# Power_Source.net
KiCad netlist of a schematic drawn in Altium Designer
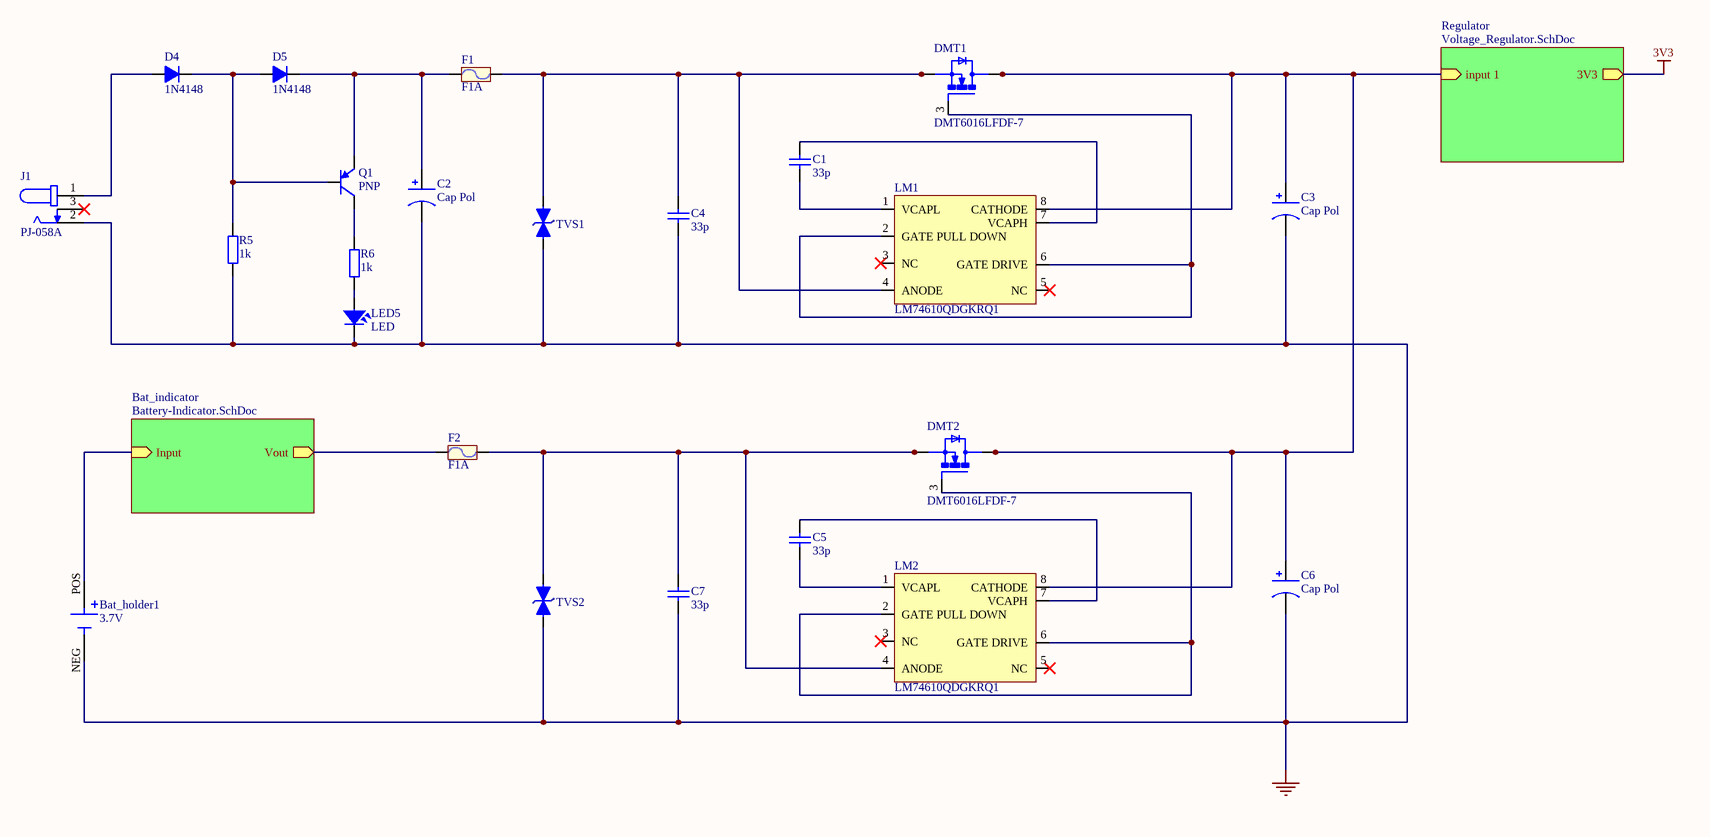
[diagram p0: Power_Source.SchDoc]

(export (version "E")
  (design (tool "Eeschema 10.0.6"))
  (components
    (comp (ref "Bat_holder1")
      (value "3.7V")
      (footprint "BAT_BK-18650-PC2")
      (description "Battery Holder (Open) 18650 1 Cell PC Pin")
      (fields (field (name "MP") "BK-18650-PC2"))
      (libsource (lib "BK-18650-PC2") (part "BK-18650-PC2"))
    )
    (comp (ref "C1")
      (value "33p")
      (footprint "CAP_CERAMIC")
      (description "Capacitor")
      (fields (field (name "Comment") "Capacitor Ceramic") (field (name "PUBLISHER") "Altium Limited"))
      (libsource (lib "My Library.~(1)") (part "CapCeramic"))
    )
    (comp (ref "C2")
      (value "Cap Pol")
      (footprint "C3MM")
      (description "Polarized Capacitor (Axial)")
      (fields (field (name "PUBLISHER") "Altium Limited"))
      (libsource (lib "My Library.~(1)") (part "Cap Pol"))
    )
    (comp (ref "C3")
      (value "Cap Pol")
      (footprint "C3MM")
      (description "Polarized Capacitor (Axial)")
      (fields (field (name "PUBLISHER") "Altium Limited"))
      (libsource (lib "My Library.~(1)") (part "Cap Pol"))
    )
    (comp (ref "C4")
      (value "33p")
      (footprint "CAP_CERAMIC")
      (description "Capacitor")
      (fields (field (name "Comment") "Capacitor Ceramic") (field (name "PUBLISHER") "Altium Limited"))
      (libsource (lib "My Library.~(1)") (part "CapCeramic"))
    )
    (comp (ref "C5")
      (value "33p")
      (footprint "CAP_CERAMIC")
      (description "Capacitor")
      (fields (field (name "Comment") "Capacitor Ceramic") (field (name "PUBLISHER") "Altium Limited"))
      (libsource (lib "My Library.~(1)") (part "CapCeramic"))
    )
    (comp (ref "C6")
      (value "Cap Pol")
      (footprint "C3MM")
      (description "Polarized Capacitor (Axial)")
      (fields (field (name "PUBLISHER") "Altium Limited"))
      (libsource (lib "My Library.~(1)") (part "Cap Pol"))
    )
    (comp (ref "C7")
      (value "33p")
      (footprint "CAP_CERAMIC")
      (description "Capacitor")
      (fields (field (name "Comment") "Capacitor Ceramic") (field (name "PUBLISHER") "Altium Limited"))
      (libsource (lib "My Library.~(1)") (part "CapCeramic"))
    )
    (comp (ref "D4")
      (value "1N4148")
      (footprint "D0.5A")
      (description "D0.5A")
      (libsource (lib "My Library.~(1)") (part "D0.5A"))
    )
    (comp (ref "D5")
      (value "1N4148")
      (footprint "D0.5A")
      (description "D0.5A")
      (libsource (lib "My Library.~(1)") (part "D0.5A"))
    )
    (comp (ref "DMT1")
      (value "DMT6016LFDF-7")
      (footprint "TRANS_DMT6016LFDF-7")
      (description "Transistor, 60V, N-channel, enhancement mode MOSFET, 60V, U-DFN2020-6 ¦ Diodes Inc DMT6016LFDF-7")
      (fields (field (name "MF") "Diodes Inc."))
      (libsource (lib "DMT6016LFDF-7") (part "DMT6016LFDF-7"))
    )
    (comp (ref "DMT2")
      (value "DMT6016LFDF-7")
      (footprint "TRANS_DMT6016LFDF-7")
      (description "Transistor, 60V, N-channel, enhancement mode MOSFET, 60V, U-DFN2020-6 ¦ Diodes Inc DMT6016LFDF-7")
      (fields (field (name "MF") "Diodes Inc."))
      (libsource (lib "DMT6016LFDF-7") (part "DMT6016LFDF-7"))
    )
    (comp (ref "F1")
      (value "F1A")
      (footprint "Fuse")
      (description "Fuse")
      (fields (field (name "DESIGNED BY") "VanDungEvn"))
      (libsource (lib "My Library.~(1)") (part "Fuse"))
    )
    (comp (ref "F2")
      (value "F1A")
      (footprint "Fuse")
      (description "Fuse")
      (fields (field (name "DESIGNED BY") "VanDungEvn"))
      (libsource (lib "My-Library") (part "Fuse"))
    )
    (comp (ref "J1")
      (value "PJ-058A")
      (footprint "CUI_PJ-058A")
      (description "2.0 x 5.7 mm, 2.5 A, Horizontal, Through Hole, Locking Type, Dc Power Jack Connector")
      (fields (field (name "MF") "Same Sky"))
      (libsource (lib "PJ-058A") (part "PJ-058A"))
    )
    (comp (ref "LED5")
      (value "LED")
      (footprint "LED-3")
      (description "LED Single colour Green and Red")
      (libsource (lib "My Library.~(1)") (part "LED"))
    )
    (comp (ref "LM1")
      (value "LM74610QDGKRQ1")
      (footprint "SOP65P490X110-8N")
      (description "0.48-V to 42-V, zero IQ automotive ideal diode controller 8-VSSOP -40 to 125")
      (fields (field (name "MANUFACTURER") "Texas Instruments"))
      (libsource (lib "VanhLib1") (part "LM74610QDGKRQ1"))
    )
    (comp (ref "LM2")
      (value "LM74610QDGKRQ1")
      (footprint "SOP65P490X110-8N")
      (description "0.48-V to 42-V, zero IQ automotive ideal diode controller 8-VSSOP -40 to 125")
      (fields (field (name "MANUFACTURER") "Texas Instruments"))
      (libsource (lib "VanhLib1") (part "LM74610QDGKRQ1"))
    )
    (comp (ref "Q1")
      (value "PNP")
      (footprint "TRAN-LOWPOWER")
      (description "PNP General")
      (fields (field (name "PUBLISHER") "Altium Limited"))
      (libsource (lib "My Library.~(1)") (part "PNP"))
    )
    (comp (ref "R5")
      (value "1k")
      (footprint "RES_0805")
      (description "Resistor SMD 0805")
      (libsource (lib "Schematic-Lib-PhilsLab") (part "RES_0805"))
    )
    (comp (ref "R6")
      (value "1k")
      (footprint "RES_0805")
      (description "Resistor SMD 0805")
      (libsource (lib "Schematic-Lib-PhilsLab") (part "RES_0805"))
    )
    (comp (ref "TVS1")
      (value "TVS")
      (footprint "CN4")
      (description "Generic TVS Diode")
      (libsource (lib "My Library.~(1)") (part "TVS"))
    )
    (comp (ref "TVS2")
      (value "TVS")
      (footprint "CN4")
      (description "Generic TVS Diode")
      (libsource (lib "My Library.~(1)") (part "TVS"))
    )
  )
  (nets
    (net (code "1") (name "/Input") (class "Default")
      (node (ref "Bat_holder1") (pin "POS") (pinfunction "POS_POS") (pintype "passive"))
    )
    (net (code "2") (name "/Vout") (class "Default")
      (node (ref "F2") (pin "1") (pinfunction "1_1") (pintype "passive"))
    )
    (net (code "3") (name "/input 1") (class "Default")
      (node (ref "C3") (pin "1") (pinfunction "1_1") (pintype "passive"))
      (node (ref "C6") (pin "1") (pinfunction "1_1") (pintype "passive"))
      (node (ref "DMT1") (pin "1") (pinfunction "D_1") (pintype "passive"))
      (node (ref "DMT1") (pin "2") (pinfunction "D_2") (pintype "passive"))
      (node (ref "DMT1") (pin "5") (pinfunction "D_5") (pintype "passive"))
      (node (ref "DMT1") (pin "6") (pinfunction "D_6") (pintype "passive"))
      (node (ref "DMT1") (pin "8") (pinfunction "D_8") (pintype "passive"))
      (node (ref "DMT2") (pin "1") (pinfunction "D_1") (pintype "passive"))
      (node (ref "DMT2") (pin "2") (pinfunction "D_2") (pintype "passive"))
      (node (ref "DMT2") (pin "5") (pinfunction "D_5") (pintype "passive"))
      (node (ref "DMT2") (pin "6") (pinfunction "D_6") (pintype "passive"))
      (node (ref "DMT2") (pin "8") (pinfunction "D_8") (pintype "passive"))
      (node (ref "LM1") (pin "8") (pinfunction "CATHODE_8") (pintype "passive"))
      (node (ref "LM2") (pin "8") (pinfunction "CATHODE_8") (pintype "passive"))
    )
    (net (code "5") (name "GND") (class "Default")
      (node (ref "Bat_holder1") (pin "NEG") (pinfunction "NEG_NEG") (pintype "passive"))
      (node (ref "C2") (pin "2") (pinfunction "2_2") (pintype "passive"))
      (node (ref "C3") (pin "2") (pinfunction "2_2") (pintype "passive"))
      (node (ref "C4") (pin "1") (pinfunction "1_1") (pintype "passive"))
      (node (ref "C6") (pin "2") (pinfunction "2_2") (pintype "passive"))
      (node (ref "C7") (pin "1") (pinfunction "1_1") (pintype "passive"))
      (node (ref "J1") (pin "2") (pinfunction "2_2") (pintype "passive"))
      (node (ref "LED5") (pin "2") (pinfunction "2_2") (pintype "passive"))
      (node (ref "R5") (pin "1") (pinfunction "1_1") (pintype "passive"))
      (node (ref "TVS1") (pin "2") (pinfunction "2_2") (pintype "passive"))
      (node (ref "TVS2") (pin "2") (pinfunction "2_2") (pintype "passive"))
    )
    (net (code "6") (name "Net-(D4-A)") (class "Default")
      (node (ref "D4") (pin "1") (pinfunction "A_1") (pintype "passive"))
      (node (ref "J1") (pin "1") (pinfunction "1_1") (pintype "passive"))
    )
    (net (code "7") (name "Net-(D4-K)") (class "Default")
      (node (ref "D4") (pin "2") (pinfunction "K_2") (pintype "passive"))
      (node (ref "D5") (pin "1") (pinfunction "A_1") (pintype "passive"))
      (node (ref "Q1") (pin "3") (pinfunction "B_3") (pintype "passive"))
      (node (ref "R5") (pin "2") (pinfunction "2_2") (pintype "passive"))
    )
    (net (code "8") (name "Net-(D5-K)") (class "Default")
      (node (ref "C2") (pin "1") (pinfunction "1_1") (pintype "passive"))
      (node (ref "D5") (pin "2") (pinfunction "K_2") (pintype "passive"))
      (node (ref "F1") (pin "1") (pinfunction "1_1") (pintype "passive"))
      (node (ref "Q1") (pin "1") (pinfunction "E_1") (pintype "passive"))
    )
    (net (code "9") (name "Net-(DMT1-G)") (class "Default")
      (node (ref "DMT1") (pin "3") (pinfunction "G_3") (pintype "passive"))
      (node (ref "LM1") (pin "2") (pinfunction "GATE_PULL_DOWN_2") (pintype "passive"))
      (node (ref "LM1") (pin "6") (pinfunction "GATE_DRIVE_6") (pintype "passive"))
    )
    (net (code "10") (name "Net-(DMT2-G)") (class "Default")
      (node (ref "DMT2") (pin "3") (pinfunction "G_3") (pintype "passive"))
      (node (ref "LM2") (pin "2") (pinfunction "GATE_PULL_DOWN_2") (pintype "passive"))
      (node (ref "LM2") (pin "6") (pinfunction "GATE_DRIVE_6") (pintype "passive"))
    )
    (net (code "11") (name "Net-(LED5-Pad1)") (class "Default")
      (node (ref "LED5") (pin "1") (pinfunction "1_1") (pintype "passive"))
      (node (ref "R6") (pin "1") (pinfunction "1_1") (pintype "passive"))
    )
    (net (code "12") (name "Net-(LM1-ANODE)") (class "Default")
      (node (ref "C4") (pin "2") (pinfunction "2_2") (pintype "passive"))
      (node (ref "DMT1") (pin "4") (pinfunction "S_4") (pintype "passive"))
      (node (ref "DMT1") (pin "7") (pinfunction "S_7") (pintype "passive"))
      (node (ref "F1") (pin "2") (pinfunction "2_2") (pintype "passive"))
      (node (ref "LM1") (pin "4") (pinfunction "ANODE_4") (pintype "passive"))
      (node (ref "TVS1") (pin "1") (pinfunction "1_1") (pintype "passive"))
    )
    (net (code "13") (name "Net-(LM1-VCAPH)") (class "Default")
      (node (ref "C1") (pin "2") (pinfunction "2_2") (pintype "passive"))
      (node (ref "LM1") (pin "7") (pinfunction "VCAPH_7") (pintype "passive"))
    )
    (net (code "14") (name "Net-(LM1-VCAPL)") (class "Default")
      (node (ref "C1") (pin "1") (pinfunction "1_1") (pintype "passive"))
      (node (ref "LM1") (pin "1") (pinfunction "VCAPL_1") (pintype "passive"))
    )
    (net (code "15") (name "Net-(LM2-ANODE)") (class "Default")
      (node (ref "C7") (pin "2") (pinfunction "2_2") (pintype "passive"))
      (node (ref "DMT2") (pin "4") (pinfunction "S_4") (pintype "passive"))
      (node (ref "DMT2") (pin "7") (pinfunction "S_7") (pintype "passive"))
      (node (ref "F2") (pin "2") (pinfunction "2_2") (pintype "passive"))
      (node (ref "LM2") (pin "4") (pinfunction "ANODE_4") (pintype "passive"))
      (node (ref "TVS2") (pin "1") (pinfunction "1_1") (pintype "passive"))
    )
    (net (code "16") (name "Net-(LM2-VCAPH)") (class "Default")
      (node (ref "C5") (pin "2") (pinfunction "2_2") (pintype "passive"))
      (node (ref "LM2") (pin "7") (pinfunction "VCAPH_7") (pintype "passive"))
    )
    (net (code "17") (name "Net-(LM2-VCAPL)") (class "Default")
      (node (ref "C5") (pin "1") (pinfunction "1_1") (pintype "passive"))
      (node (ref "LM2") (pin "1") (pinfunction "VCAPL_1") (pintype "passive"))
    )
    (net (code "18") (name "Net-(Q1-C)") (class "Default")
      (node (ref "Q1") (pin "2") (pinfunction "C_2") (pintype "passive"))
      (node (ref "R6") (pin "2") (pinfunction "2_2") (pintype "passive"))
    )
    (net (code "19") (name "unconnected-(J1-Pad3)") (class "Default")
      (node (ref "J1") (pin "3") (pinfunction "3_3") (pintype "passive+no_connect"))
    )
    (net (code "20") (name "unconnected-(LM1-NC-Pad3)") (class "Default")
      (node (ref "LM1") (pin "3") (pinfunction "NC_3") (pintype "passive+no_connect"))
    )
    (net (code "21") (name "unconnected-(LM1-NC-Pad5)") (class "Default")
      (node (ref "LM1") (pin "5") (pinfunction "NC_5") (pintype "passive+no_connect"))
    )
    (net (code "22") (name "unconnected-(LM2-NC-Pad3)") (class "Default")
      (node (ref "LM2") (pin "3") (pinfunction "NC_3") (pintype "passive+no_connect"))
    )
    (net (code "23") (name "unconnected-(LM2-NC-Pad5)") (class "Default")
      (node (ref "LM2") (pin "5") (pinfunction "NC_5") (pintype "passive+no_connect"))
    )
  )
)
